# Step-to-Talk.net
KiCad netlist of a schematic drawn in EAGLE
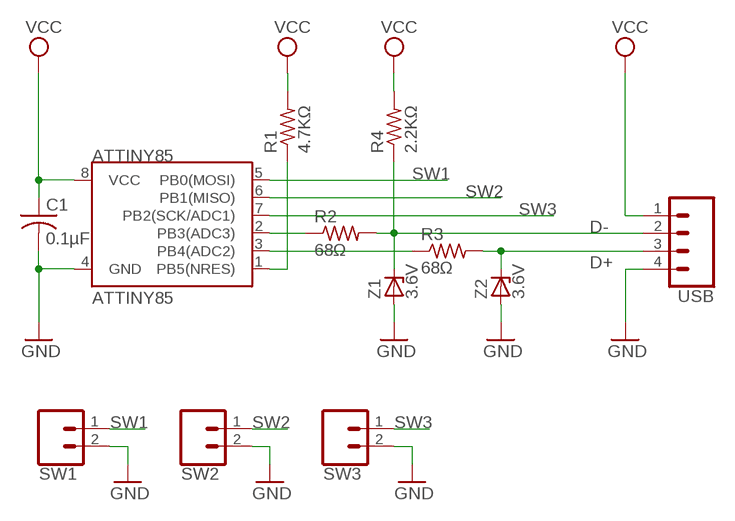
[diagram p0: schematic, sheet 1]

(export (version "E")
  (design (tool "Eeschema 10.0.6"))
  (components
    (comp (ref "ATTINY85")
      (value "ATTINY85")
      (footprint "eagle-import:DIP08_MCU")
      (libsource (lib "eagle-import") (part "ATTINY45TINY85-20-DIP"))
    )
    (comp (ref "C1")
      (value "0.1µF")
      (footprint "eagle-import:C025-024X044")
      (libsource (lib "eagle-import") (part "C-US025-024X044"))
    )
    (comp (ref "R1")
      (value "4.7KΩ")
      (footprint "eagle-import:0204_5")
      (libsource (lib "eagle-import") (part "R-US_0204/5"))
    )
    (comp (ref "R2")
      (value "68Ω")
      (footprint "eagle-import:0204_5")
      (libsource (lib "eagle-import") (part "R-US_0204/5"))
    )
    (comp (ref "R3")
      (value "68Ω")
      (footprint "eagle-import:0204_5")
      (libsource (lib "eagle-import") (part "R-US_0204/5"))
    )
    (comp (ref "R4")
      (value "2.2KΩ")
      (footprint "eagle-import:0204_5")
      (libsource (lib "eagle-import") (part "R-US_0204/5"))
    )
    (comp (ref "SW1")
      (value "CONN_02")
      (footprint "eagle-import:1X02")
      (libsource (lib "eagle-import") (part "CONN_02"))
    )
    (comp (ref "SW2")
      (value "CONN_02")
      (footprint "eagle-import:1X02")
      (libsource (lib "eagle-import") (part "CONN_02"))
    )
    (comp (ref "SW3")
      (value "CONN_02")
      (footprint "eagle-import:1X02")
      (libsource (lib "eagle-import") (part "CONN_02"))
    )
    (comp (ref "USB")
      (value "CONN_04LONGPADS")
      (footprint "eagle-import:1X04_LONGPADS")
      (libsource (lib "eagle-import") (part "CONN_04LONGPADS"))
    )
    (comp (ref "Z1")
      (value "3.6V")
      (footprint "eagle-import:ZDIO-5")
      (libsource (lib "eagle-import") (part "ZENER-DIODEZD-5"))
    )
    (comp (ref "Z2")
      (value "3.6V")
      (footprint "eagle-import:ZDIO-5")
      (libsource (lib "eagle-import") (part "ZENER-DIODEZD-5"))
    )
  )
  (nets
    (net (code "1") (name "/D+") (class "Default")
      (node (ref "R3") (pin "2") (pinfunction "2_2") (pintype "passive"))
      (node (ref "USB") (pin "3") (pinfunction "3_3") (pintype "passive"))
      (node (ref "Z2") (pin "C") (pinfunction "C_C") (pintype "passive"))
    )
    (net (code "2") (name "/D-") (class "Default")
      (node (ref "R2") (pin "2") (pinfunction "2_2") (pintype "passive"))
      (node (ref "R4") (pin "1") (pinfunction "1_1") (pintype "passive"))
      (node (ref "USB") (pin "2") (pinfunction "2_2") (pintype "passive"))
      (node (ref "Z1") (pin "C") (pinfunction "C_C") (pintype "passive"))
    )
    (net (code "3") (name "/SW1") (class "Default")
      (node (ref "ATTINY85") (pin "5") (pinfunction "PB0(MOSI)_5") (pintype "bidirectional"))
      (node (ref "SW1") (pin "1") (pinfunction "1_1") (pintype "passive"))
    )
    (net (code "4") (name "/SW2") (class "Default")
      (node (ref "ATTINY85") (pin "6") (pinfunction "PB1(MISO)_6") (pintype "bidirectional"))
      (node (ref "SW2") (pin "1") (pinfunction "1_1") (pintype "passive"))
    )
    (net (code "5") (name "/SW3") (class "Default")
      (node (ref "ATTINY85") (pin "7") (pinfunction "PB2(SCK/ADC1)_7") (pintype "bidirectional"))
      (node (ref "SW3") (pin "1") (pinfunction "1_1") (pintype "passive"))
    )
    (net (code "6") (name "GND") (class "Default")
      (node (ref "ATTINY85") (pin "4") (pinfunction "GND_4") (pintype "bidirectional"))
      (node (ref "C1") (pin "2") (pinfunction "2_2") (pintype "passive"))
      (node (ref "SW1") (pin "2") (pinfunction "2_2") (pintype "passive"))
      (node (ref "SW2") (pin "2") (pinfunction "2_2") (pintype "passive"))
      (node (ref "SW3") (pin "2") (pinfunction "2_2") (pintype "passive"))
      (node (ref "USB") (pin "4") (pinfunction "4_4") (pintype "passive"))
      (node (ref "Z1") (pin "A") (pinfunction "A_A") (pintype "passive"))
      (node (ref "Z2") (pin "A") (pinfunction "A_A") (pintype "passive"))
    )
    (net (code "7") (name "Net-(ATTINY85-PB3(ADC3))") (class "Default")
      (node (ref "ATTINY85") (pin "2") (pinfunction "PB3(ADC3)_2") (pintype "bidirectional"))
      (node (ref "R2") (pin "1") (pinfunction "1_1") (pintype "passive"))
    )
    (net (code "8") (name "Net-(ATTINY85-PB4(ADC2))") (class "Default")
      (node (ref "ATTINY85") (pin "3") (pinfunction "PB4(ADC2)_3") (pintype "bidirectional"))
      (node (ref "R3") (pin "1") (pinfunction "1_1") (pintype "passive"))
    )
    (net (code "9") (name "Net-(ATTINY85-PB5(NRES))") (class "Default")
      (node (ref "ATTINY85") (pin "1") (pinfunction "PB5(NRES)_1") (pintype "bidirectional"))
      (node (ref "R1") (pin "1") (pinfunction "1_1") (pintype "passive"))
    )
    (net (code "10") (name "VCC") (class "Default")
      (node (ref "ATTINY85") (pin "8") (pinfunction "VCC_8") (pintype "bidirectional"))
      (node (ref "C1") (pin "1") (pinfunction "1_1") (pintype "passive"))
      (node (ref "R1") (pin "2") (pinfunction "2_2") (pintype "passive"))
      (node (ref "R4") (pin "2") (pinfunction "2_2") (pintype "passive"))
      (node (ref "USB") (pin "1") (pinfunction "1_1") (pintype "passive"))
    )
  )
)
